# Lightproject.net
KiCad netlist of a schematic drawn in Altium Designer
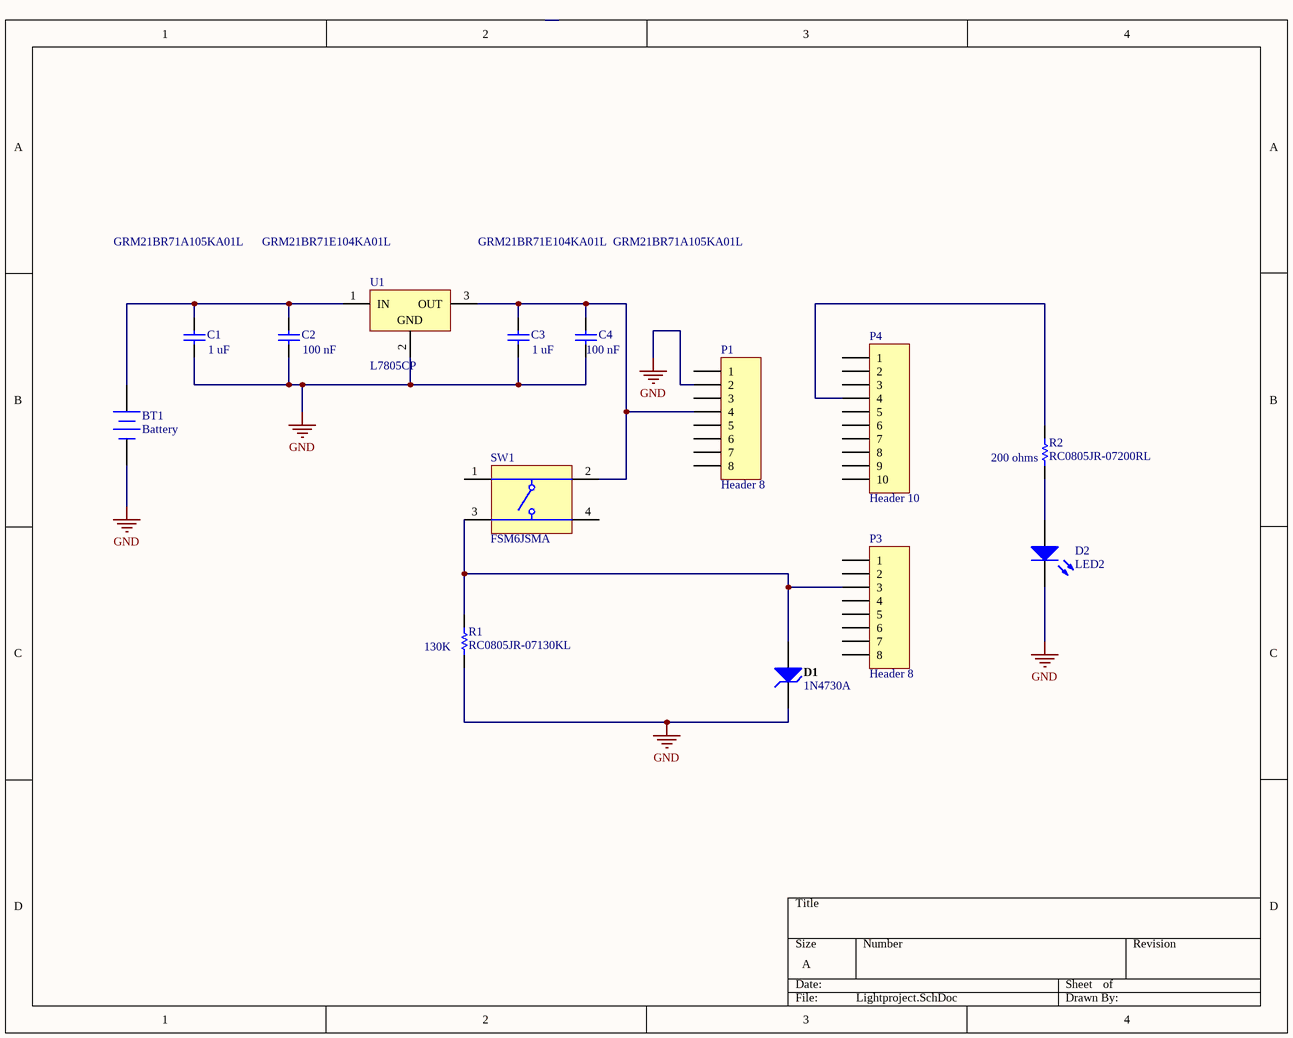
[diagram p0: Lightproject.SchDoc]

(export (version "E")
  (design (tool "Eeschema 10.0.6"))
  (components
    (comp (ref "BT1")
      (value "Battery")
      (footprint "BAT-2")
      (description "Multicell Battery")
      (fields (field (name "PUBLISHER") "Altium Limited"))
      (libsource (lib "Miscellaneous Devices") (part "Battery"))
    )
    (comp (ref "C1")
      (value "GRM21BR71A105KA01L")
      (footprint "CAPC2013X135X45NL10T25")
      (fields (field (name "MANUFACTURER") "Murata"))
      (libsource (lib "Altium Content Vault") (part "CAP"))
    )
    (comp (ref "C2")
      (value "GRM21BR71E104KA01L")
      (footprint "CAPC2013X135X50ML10T20")
      (fields (field (name "MANUFACTURER") "Murata"))
      (libsource (lib "Altium Content Vault") (part "CAP"))
    )
    (comp (ref "C3")
      (value "GRM21BR71E104KA01L")
      (footprint "CAPC2013X135X50ML10T20")
      (fields (field (name "MANUFACTURER") "Murata"))
      (libsource (lib "Altium Content Vault") (part "CAP"))
    )
    (comp (ref "C4")
      (value "GRM21BR71A105KA01L")
      (footprint "CAPC2013X135X45NL10T25")
      (fields (field (name "MANUFACTURER") "Murata"))
      (libsource (lib "Altium Content Vault") (part "CAP"))
    )
    (comp (ref "D1")
      (value "1N4730A")
      (footprint "FAIR-DO-41-2_V")
      (description "Zener Diode, 3.9V, 1W, 5%, -65 to 200 degC, 2-Pin DO-41, Body 2.72 x 5.2 mm, RoHS")
      (fields (field (name "TOLERANCE") "5%") (field (name "MANUFACTURER") "Fairchild Semiconductor"))
      (libsource (lib "Altium Content Vault") (part "FAIR-DZEN-A1K2-2"))
    )
    (comp (ref "D2")
      (value "LED2")
      (footprint "3.2X1.6X1.1")
      (description "Typical RED, GREEN, YELLOW, AMBER GaAs LED")
      (fields (field (name "PUBLISHER") "Altium Limited"))
      (libsource (lib "Miscellaneous Devices") (part "LED2"))
    )
    (comp (ref "P1")
      (value "Header 8")
      (footprint "HDR1X8")
      (description "Header, 8-Pin")
      (fields (field (name "PUBLISHER") "Altium Limited"))
      (libsource (lib "Miscellaneous Connectors") (part "Header 8"))
    )
    (comp (ref "P3")
      (value "Header 8")
      (footprint "HDR1X8")
      (description "Header, 8-Pin")
      (fields (field (name "PUBLISHER") "Altium Limited"))
      (libsource (lib "Miscellaneous Connectors") (part "Header 8"))
    )
    (comp (ref "P4")
      (value "Header 10")
      (footprint "HDR1X10")
      (description "Header, 10-Pin")
      (fields (field (name "PUBLISHER") "Altium Limited"))
      (libsource (lib "Miscellaneous Connectors") (part "Header 10"))
    )
    (comp (ref "R1")
      (value "RC0805JR-07130KL")
      (footprint "RESC2013X60X35NL10T20")
      (fields (field (name "MANUFACTURER") "Yageo"))
      (libsource (lib "Altium Content Vault") (part "RES"))
    )
    (comp (ref "R2")
      (value "RC0805JR-07200RL")
      (footprint "RESC2013X60X35ML10T20")
      (fields (field (name "MANUFACTURER") "Yageo"))
      (libsource (lib "Altium Content Vault") (part "RES"))
    )
    (comp (ref "SW1")
      (value "FSM6JSMA")
      (footprint "TECO-FSM6JSMA_V")
      (description "Switch, SPST, 24 V, -35 to 85 degC, 4-Pin SMD, RoHS, Tape and Reel")
      (fields (field (name "MANUFACTURER") "TE Connectivity"))
      (libsource (lib "Altium Content Vault") (part "SW-SPST-4_A"))
    )
    (comp (ref "U1")
      (value "L7805CP")
      (footprint "TO220FP")
      (description "Positive Voltage Regulator, 5V, 3-Pin TO-220FP")
      (libsource (lib "Altium Content Vault") (part "PM-REG-L4940-SIL3"))
    )
  )
  (nets
    (net (code "1") (name "GND") (class "Default")
      (node (ref "BT1") (pin "2") (pinfunction "-_2") (pintype "passive"))
      (node (ref "C1") (pin "1") (pinfunction "1_1") (pintype "passive"))
      (node (ref "C2") (pin "1") (pinfunction "1_1") (pintype "passive"))
      (node (ref "C3") (pin "1") (pinfunction "1_1") (pintype "passive"))
      (node (ref "C4") (pin "1") (pinfunction "1_1") (pintype "passive"))
      (node (ref "D1") (pin "2") (pinfunction "K_2") (pintype "passive"))
      (node (ref "D2") (pin "2") (pinfunction "K_2") (pintype "passive"))
      (node (ref "P1") (pin "2") (pinfunction "2_2") (pintype "passive"))
      (node (ref "R1") (pin "1") (pinfunction "1_1") (pintype "passive"))
      (node (ref "U1") (pin "2") (pinfunction "GND_2") (pintype "power_in"))
    )
    (net (code "2") (name "Net-(BT1-+)") (class "Default")
      (node (ref "BT1") (pin "1") (pinfunction "+_1") (pintype "passive"))
      (node (ref "C1") (pin "2") (pinfunction "2_2") (pintype "passive"))
      (node (ref "C2") (pin "2") (pinfunction "2_2") (pintype "passive"))
      (node (ref "U1") (pin "1") (pinfunction "IN_1") (pintype "power_in"))
    )
    (net (code "3") (name "Net-(D1-A)") (class "Default")
      (node (ref "D1") (pin "1") (pinfunction "A_1") (pintype "passive"))
      (node (ref "P3") (pin "3") (pinfunction "3_3") (pintype "passive"))
      (node (ref "R1") (pin "2") (pinfunction "2_2") (pintype "passive"))
      (node (ref "SW1") (pin "3") (pinfunction "3_3") (pintype "passive"))
    )
    (net (code "4") (name "Net-(D2-A)") (class "Default")
      (node (ref "D2") (pin "1") (pinfunction "A_1") (pintype "passive"))
      (node (ref "R2") (pin "1") (pinfunction "1_1") (pintype "passive"))
    )
    (net (code "5") (name "Net-(P4-Pad4)") (class "Default")
      (node (ref "P4") (pin "4") (pinfunction "4_4") (pintype "passive"))
      (node (ref "R2") (pin "2") (pinfunction "2_2") (pintype "passive"))
    )
    (net (code "6") (name "Net-(U1-OUT)") (class "Default")
      (node (ref "C3") (pin "2") (pinfunction "2_2") (pintype "passive"))
      (node (ref "C4") (pin "2") (pinfunction "2_2") (pintype "passive"))
      (node (ref "P1") (pin "4") (pinfunction "4_4") (pintype "passive"))
      (node (ref "SW1") (pin "2") (pinfunction "2_2") (pintype "passive"))
      (node (ref "U1") (pin "3") (pinfunction "OUT_3") (pintype "power_in"))
    )
    (net (code "7") (name "unconnected-(P1-Pad1)") (class "Default")
      (node (ref "P1") (pin "1") (pinfunction "1_1") (pintype "passive"))
    )
    (net (code "8") (name "unconnected-(P1-Pad3)") (class "Default")
      (node (ref "P1") (pin "3") (pinfunction "3_3") (pintype "passive"))
    )
    (net (code "9") (name "unconnected-(P1-Pad5)") (class "Default")
      (node (ref "P1") (pin "5") (pinfunction "5_5") (pintype "passive"))
    )
    (net (code "10") (name "unconnected-(P1-Pad6)") (class "Default")
      (node (ref "P1") (pin "6") (pinfunction "6_6") (pintype "passive"))
    )
    (net (code "11") (name "unconnected-(P1-Pad7)") (class "Default")
      (node (ref "P1") (pin "7") (pinfunction "7_7") (pintype "passive"))
    )
    (net (code "12") (name "unconnected-(P1-Pad8)") (class "Default")
      (node (ref "P1") (pin "8") (pinfunction "8_8") (pintype "passive"))
    )
    (net (code "13") (name "unconnected-(P3-Pad1)") (class "Default")
      (node (ref "P3") (pin "1") (pinfunction "1_1") (pintype "passive"))
    )
    (net (code "14") (name "unconnected-(P3-Pad2)") (class "Default")
      (node (ref "P3") (pin "2") (pinfunction "2_2") (pintype "passive"))
    )
    (net (code "15") (name "unconnected-(P3-Pad4)") (class "Default")
      (node (ref "P3") (pin "4") (pinfunction "4_4") (pintype "passive"))
    )
    (net (code "16") (name "unconnected-(P3-Pad5)") (class "Default")
      (node (ref "P3") (pin "5") (pinfunction "5_5") (pintype "passive"))
    )
    (net (code "17") (name "unconnected-(P3-Pad6)") (class "Default")
      (node (ref "P3") (pin "6") (pinfunction "6_6") (pintype "passive"))
    )
    (net (code "18") (name "unconnected-(P3-Pad7)") (class "Default")
      (node (ref "P3") (pin "7") (pinfunction "7_7") (pintype "passive"))
    )
    (net (code "19") (name "unconnected-(P3-Pad8)") (class "Default")
      (node (ref "P3") (pin "8") (pinfunction "8_8") (pintype "passive"))
    )
    (net (code "20") (name "unconnected-(P4-Pad1)") (class "Default")
      (node (ref "P4") (pin "1") (pinfunction "1_1") (pintype "passive"))
    )
    (net (code "21") (name "unconnected-(P4-Pad2)") (class "Default")
      (node (ref "P4") (pin "2") (pinfunction "2_2") (pintype "passive"))
    )
    (net (code "22") (name "unconnected-(P4-Pad3)") (class "Default")
      (node (ref "P4") (pin "3") (pinfunction "3_3") (pintype "passive"))
    )
    (net (code "23") (name "unconnected-(P4-Pad5)") (class "Default")
      (node (ref "P4") (pin "5") (pinfunction "5_5") (pintype "passive"))
    )
    (net (code "24") (name "unconnected-(P4-Pad6)") (class "Default")
      (node (ref "P4") (pin "6") (pinfunction "6_6") (pintype "passive"))
    )
    (net (code "25") (name "unconnected-(P4-Pad7)") (class "Default")
      (node (ref "P4") (pin "7") (pinfunction "7_7") (pintype "passive"))
    )
    (net (code "26") (name "unconnected-(P4-Pad8)") (class "Default")
      (node (ref "P4") (pin "8") (pinfunction "8_8") (pintype "passive"))
    )
    (net (code "27") (name "unconnected-(P4-Pad9)") (class "Default")
      (node (ref "P4") (pin "9") (pinfunction "9_9") (pintype "passive"))
    )
    (net (code "28") (name "unconnected-(P4-Pad10)") (class "Default")
      (node (ref "P4") (pin "10") (pinfunction "10_10") (pintype "passive"))
    )
    (net (code "29") (name "unconnected-(SW1-Pad1)") (class "Default")
      (node (ref "SW1") (pin "1") (pinfunction "1_1") (pintype "passive"))
    )
    (net (code "30") (name "unconnected-(SW1-Pad4)") (class "Default")
      (node (ref "SW1") (pin "4") (pinfunction "4_4") (pintype "passive"))
    )
  )
)
